# USB_UART.net
KiCad netlist of a schematic drawn in Altium Designer
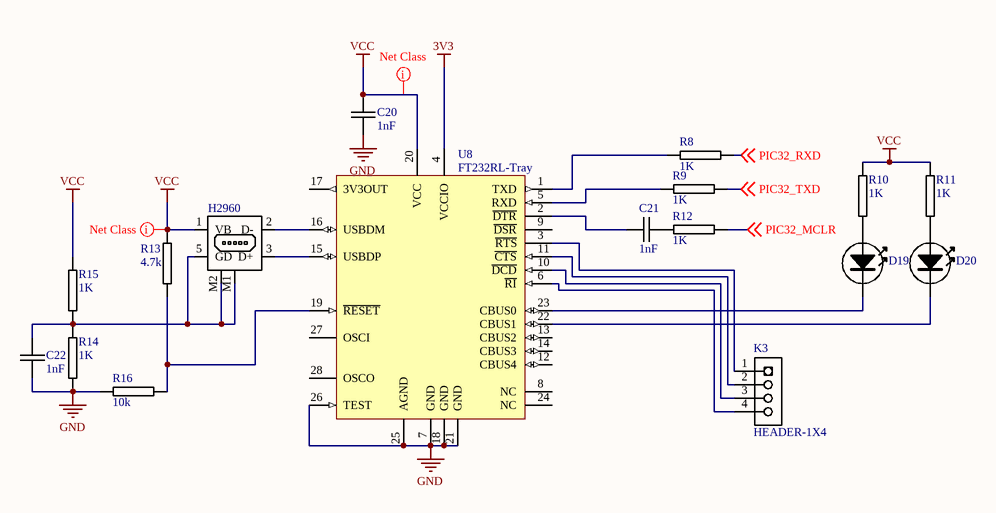
[diagram p0: USB_UART.SchDoc]

(export (version "E")
  (design (tool "Eeschema 10.0.6"))
  (components
    (comp (ref "C20")
      (value "1nF")
      (footprint "0603C-GENERIC")
      (description "CAPACITOR 0603 CERAMIC")
      (libsource (lib "vh_altium_library") (part "0603C-000"))
    )
    (comp (ref "C21")
      (value "1nF")
      (footprint "0603C-GENERIC")
      (description "CAPACITOR 0603 CERAMIC")
      (libsource (lib "vh_altium_library") (part "0603C-000"))
    )
    (comp (ref "C22")
      (value "1nF")
      (footprint "0603C-GENERIC")
      (description "CAPACITOR 0603 CERAMIC")
      (libsource (lib "vh_altium_library") (part "0603C-000"))
    )
    (comp (ref "D19")
      (value "TOPLED-RED")
      (footprint "TOPLED-RED")
      (fields
        (field (name "MANUFACTURER") "OSRAM Opto Semiconductors Inc")
        (field (name "MANUFACTURER PART NUMBER") "LS T676-Q1R2-1-Z")
      )
      (libsource (lib "vh_altium_library") (part "TOPLED-RED"))
    )
    (comp (ref "D20")
      (value "TOPLED-RED")
      (footprint "TOPLED-RED")
      (fields
        (field (name "MANUFACTURER") "OSRAM Opto Semiconductors Inc")
        (field (name "MANUFACTURER PART NUMBER") "LS T676-Q1R2-1-Z")
      )
      (libsource (lib "vh_altium_library") (part "TOPLED-RED"))
    )
    (comp (ref "K1")
      (value "H2960")
      (footprint "usb-mini-b")
      (description "MINI USB B DEVICE CONNECTOR")
      (libsource (lib "vh_altium_library") (part "USB-H2960"))
    )
    (comp (ref "K3")
      (value "HEADER-1X4")
      (footprint "HEADER-1X4")
      (libsource (lib "vh_altium_library") (part "HEADER-1X4"))
    )
    (comp (ref "R8")
      (value "1K")
      (footprint "0603R-1k")
      (description "GENERIC RESISTOR 0603")
      (fields
        (field (name "MANUFACTURER PART NUMBER") "RMCF 1/16 1K 1% R")
        (field (name "MANUFACTURER") "Stackpole Electronics Inc")
      )
      (libsource (lib "vh_altium_library") (part "0603R-1K"))
    )
    (comp (ref "R9")
      (value "1K")
      (footprint "0603R-1k")
      (description "GENERIC RESISTOR 0603")
      (fields
        (field (name "MANUFACTURER PART NUMBER") "RMCF 1/16 1K 1% R")
        (field (name "MANUFACTURER") "Stackpole Electronics Inc")
      )
      (libsource (lib "vh_altium_library") (part "0603R-1K"))
    )
    (comp (ref "R10")
      (value "1K")
      (footprint "0603R-1k")
      (description "GENERIC RESISTOR 0603")
      (fields
        (field (name "MANUFACTURER PART NUMBER") "RMCF 1/16 1K 1% R")
        (field (name "MANUFACTURER") "Stackpole Electronics Inc")
      )
      (libsource (lib "vh_altium_library") (part "0603R-1K"))
    )
    (comp (ref "R11")
      (value "1K")
      (footprint "0603R-1k")
      (description "GENERIC RESISTOR 0603")
      (fields
        (field (name "MANUFACTURER PART NUMBER") "RMCF 1/16 1K 1% R")
        (field (name "MANUFACTURER") "Stackpole Electronics Inc")
      )
      (libsource (lib "vh_altium_library") (part "0603R-1K"))
    )
    (comp (ref "R12")
      (value "1K")
      (footprint "0603R-1k")
      (description "GENERIC RESISTOR 0603")
      (fields
        (field (name "MANUFACTURER PART NUMBER") "RMCF 1/16 1K 1% R")
        (field (name "MANUFACTURER") "Stackpole Electronics Inc")
      )
      (libsource (lib "vh_altium_library") (part "0603R-1K"))
    )
    (comp (ref "R13")
      (value "4.7k")
      (footprint "0603R-1k")
      (description "GENERIC RESISTOR 0603")
      (fields
        (field (name "MANUFACTURER PART NUMBER") "RMCF 1/16 1K 1% R")
        (field (name "MANUFACTURER") "Stackpole Electronics Inc")
      )
      (libsource (lib "vh_altium_library") (part "0603R-1K"))
    )
    (comp (ref "R14")
      (value "1K")
      (footprint "0603R-1k")
      (description "GENERIC RESISTOR 0603")
      (fields
        (field (name "MANUFACTURER PART NUMBER") "RMCF 1/16 1K 1% R")
        (field (name "MANUFACTURER") "Stackpole Electronics Inc")
      )
      (libsource (lib "vh_altium_library") (part "0603R-1K"))
    )
    (comp (ref "R15")
      (value "1K")
      (footprint "0603R-1k")
      (description "GENERIC RESISTOR 0603")
      (fields
        (field (name "MANUFACTURER PART NUMBER") "RMCF 1/16 1K 1% R")
        (field (name "MANUFACTURER") "Stackpole Electronics Inc")
      )
      (libsource (lib "vh_altium_library") (part "0603R-1K"))
    )
    (comp (ref "R16")
      (value "10k")
      (footprint "0603R-1k")
      (description "GENERIC RESISTOR 0603")
      (fields
        (field (name "MANUFACTURER PART NUMBER") "RMCF 1/16 1K 1% R")
        (field (name "MANUFACTURER") "Stackpole Electronics Inc")
      )
      (libsource (lib "vh_altium_library") (part "0603R-1K"))
    )
    (comp (ref "U8")
      (value "FT232RL-Tray")
      (footprint "SSOP-28_N")
      (description "USB UART Asynchronous Serial Data Transfer Chip, SSOP-28, Tray")
      (fields (field (name "PUBLISHER") "Altium Limited"))
      (libsource (lib "FTDI Communication UART") (part "FT232RL-Tray"))
    )
  )
  (nets
    (net (code "1") (name "3V3") (class "Default")
      (node (ref "U8") (pin "4") (pinfunction "VCCIO_4") (pintype "power_in"))
    )
    (net (code "2") (name "GND") (class "Default")
      (node (ref "C20") (pin "2") (pintype "passive"))
      (node (ref "C22") (pin "2") (pintype "passive"))
      (node (ref "R14") (pin "2") (pintype "passive"))
      (node (ref "R16") (pin "2") (pintype "passive"))
      (node (ref "U8") (pin "18") (pinfunction "GND_18") (pintype "power_in"))
      (node (ref "U8") (pin "21") (pinfunction "GND_21") (pintype "power_in"))
      (node (ref "U8") (pin "25") (pinfunction "AGND_25") (pintype "power_in"))
      (node (ref "U8") (pin "26") (pinfunction "TEST_26") (pintype "input"))
      (node (ref "U8") (pin "7") (pinfunction "GND_7") (pintype "power_in"))
    )
    (net (code "3") (name "Net-(D19-PadA)") (class "Default")
      (node (ref "D19") (pin "A") (pintype "passive"))
      (node (ref "R10") (pin "1") (pintype "passive"))
    )
    (net (code "4") (name "Net-(D20-PadA)") (class "Default")
      (node (ref "D20") (pin "A") (pintype "passive"))
      (node (ref "R11") (pin "1") (pintype "passive"))
    )
    (net (code "5") (name "Net-(K1-D+)") (class "Default")
      (node (ref "K1") (pin "3") (pinfunction "D+_3") (pintype "passive"))
      (node (ref "U8") (pin "15") (pinfunction "USBDP_15") (pintype "bidirectional"))
    )
    (net (code "6") (name "Net-(K1-D-)") (class "Default")
      (node (ref "K1") (pin "2") (pinfunction "D-_2") (pintype "passive"))
      (node (ref "U8") (pin "16") (pinfunction "USBDM_16") (pintype "bidirectional"))
    )
    (net (code "7") (name "Net-(K1-GD)") (class "Default")
      (node (ref "C22") (pin "1") (pintype "passive"))
      (node (ref "K1") (pin "5") (pinfunction "GD_5") (pintype "passive"))
      (node (ref "K1") (pin "M1") (pintype "passive"))
      (node (ref "K1") (pin "M2") (pintype "passive"))
      (node (ref "R14") (pin "1") (pintype "passive"))
      (node (ref "R15") (pin "2") (pintype "passive"))
    )
    (net (code "8") (name "Net-(U8-CBUS0)") (class "Default")
      (node (ref "D19") (pin "K") (pintype "passive"))
      (node (ref "U8") (pin "23") (pinfunction "CBUS0_23") (pintype "bidirectional"))
    )
    (net (code "9") (name "Net-(U8-CBUS1)") (class "Default")
      (node (ref "D20") (pin "K") (pintype "passive"))
      (node (ref "U8") (pin "22") (pinfunction "CBUS1_22") (pintype "bidirectional"))
    )
    (net (code "10") (name "Net-(U8-RXD)") (class "Default")
      (node (ref "R9") (pin "1") (pintype "passive"))
      (node (ref "U8") (pin "5") (pinfunction "RXD_5") (pintype "input"))
    )
    (net (code "11") (name "Net-(U8-TXD)") (class "Default")
      (node (ref "R8") (pin "1") (pintype "passive"))
      (node (ref "U8") (pin "1") (pinfunction "TXD_1") (pintype "output"))
    )
    (net (code "12") (name "Net-(U8-~{CTS})") (class "Default")
      (node (ref "K3") (pin "2") (pintype "passive"))
      (node (ref "U8") (pin "11") (pinfunction "~{CTS}_11") (pintype "input"))
    )
    (net (code "13") (name "Net-(U8-~{DCD})") (class "Default")
      (node (ref "K3") (pin "3") (pintype "passive"))
      (node (ref "U8") (pin "10") (pinfunction "~{DCD}_10") (pintype "input"))
    )
    (net (code "14") (name "Net-(U8-~{DTR})") (class "Default")
      (node (ref "C21") (pin "1") (pintype "passive"))
      (node (ref "U8") (pin "2") (pinfunction "~{DTR}_2") (pintype "passive"))
    )
    (net (code "15") (name "Net-(U8-~{RESET})") (class "Default")
      (node (ref "R13") (pin "2") (pintype "passive"))
      (node (ref "R16") (pin "1") (pintype "passive"))
      (node (ref "U8") (pin "19") (pinfunction "~{RESET}_19") (pintype "input"))
    )
    (net (code "16") (name "Net-(U8-~{RI})") (class "Default")
      (node (ref "K3") (pin "4") (pintype "passive"))
      (node (ref "U8") (pin "6") (pinfunction "~{RI}_6") (pintype "input"))
    )
    (net (code "17") (name "Net-(U8-~{RTS})") (class "Default")
      (node (ref "K3") (pin "1") (pintype "passive"))
      (node (ref "U8") (pin "3") (pinfunction "~{RTS}_3") (pintype "passive"))
    )
    (net (code "18") (name "PIC32_MCLR") (class "Default") (node (ref "R12") (pin "2") (pintype "passive")))
    (net (code "19") (name "PIC32_RXD") (class "Default") (node (ref "R8") (pin "2") (pintype "passive")))
    (net (code "20") (name "PIC32_TXD") (class "Default") (node (ref "R9") (pin "2") (pintype "passive")))
    (net (code "21") (name "VCC") (class "Default")
      (node (ref "C20") (pin "1") (pintype "passive"))
      (node (ref "K1") (pin "1") (pinfunction "VB_1") (pintype "passive"))
      (node (ref "R10") (pin "2") (pintype "passive"))
      (node (ref "R11") (pin "2") (pintype "passive"))
      (node (ref "R13") (pin "1") (pintype "passive"))
      (node (ref "R15") (pin "1") (pintype "passive"))
      (node (ref "U8") (pin "20") (pinfunction "VCC_20") (pintype "power_in"))
    )
    (net (code "22") (name "unconnected-(C21-Pad2)") (class "Default")
      (node (ref "C21") (pin "2") (pintype "passive"))
    )
    (net (code "23") (name "unconnected-(R12-Pad1)") (class "Default")
      (node (ref "R12") (pin "1") (pintype "passive"))
    )
    (net (code "24") (name "unconnected-(U8-3V3OUT-Pad17)") (class "Default")
      (node (ref "U8") (pin "17") (pinfunction "3V3OUT_17") (pintype "output"))
    )
    (net (code "25") (name "unconnected-(U8-CBUS2-Pad13)") (class "Default")
      (node (ref "U8") (pin "13") (pinfunction "CBUS2_13") (pintype "bidirectional"))
    )
    (net (code "26") (name "unconnected-(U8-CBUS3-Pad14)") (class "Default")
      (node (ref "U8") (pin "14") (pinfunction "CBUS3_14") (pintype "bidirectional"))
    )
    (net (code "27") (name "unconnected-(U8-CBUS4-Pad12)") (class "Default")
      (node (ref "U8") (pin "12") (pinfunction "CBUS4_12") (pintype "bidirectional"))
    )
    (net (code "28") (name "unconnected-(U8-NC-Pad8)") (class "Default")
      (node (ref "U8") (pin "8") (pinfunction "NC_8") (pintype "passive"))
    )
    (net (code "29") (name "unconnected-(U8-NC-Pad24)") (class "Default")
      (node (ref "U8") (pin "24") (pinfunction "NC_24") (pintype "passive"))
    )
    (net (code "30") (name "unconnected-(U8-OSCI-Pad27)") (class "Default")
      (node (ref "U8") (pin "27") (pinfunction "OSCI_27") (pintype "passive"))
    )
    (net (code "31") (name "unconnected-(U8-OSCO-Pad28)") (class "Default")
      (node (ref "U8") (pin "28") (pinfunction "OSCO_28") (pintype "passive"))
    )
    (net (code "32") (name "unconnected-(U8-~{DSR}-Pad9)") (class "Default")
      (node (ref "U8") (pin "9") (pinfunction "~{DSR}_9") (pintype "passive"))
    )
  )
)
